# RoketAnaSistemSematik.net
KiCad netlist of a schematic drawn in Altium Designer
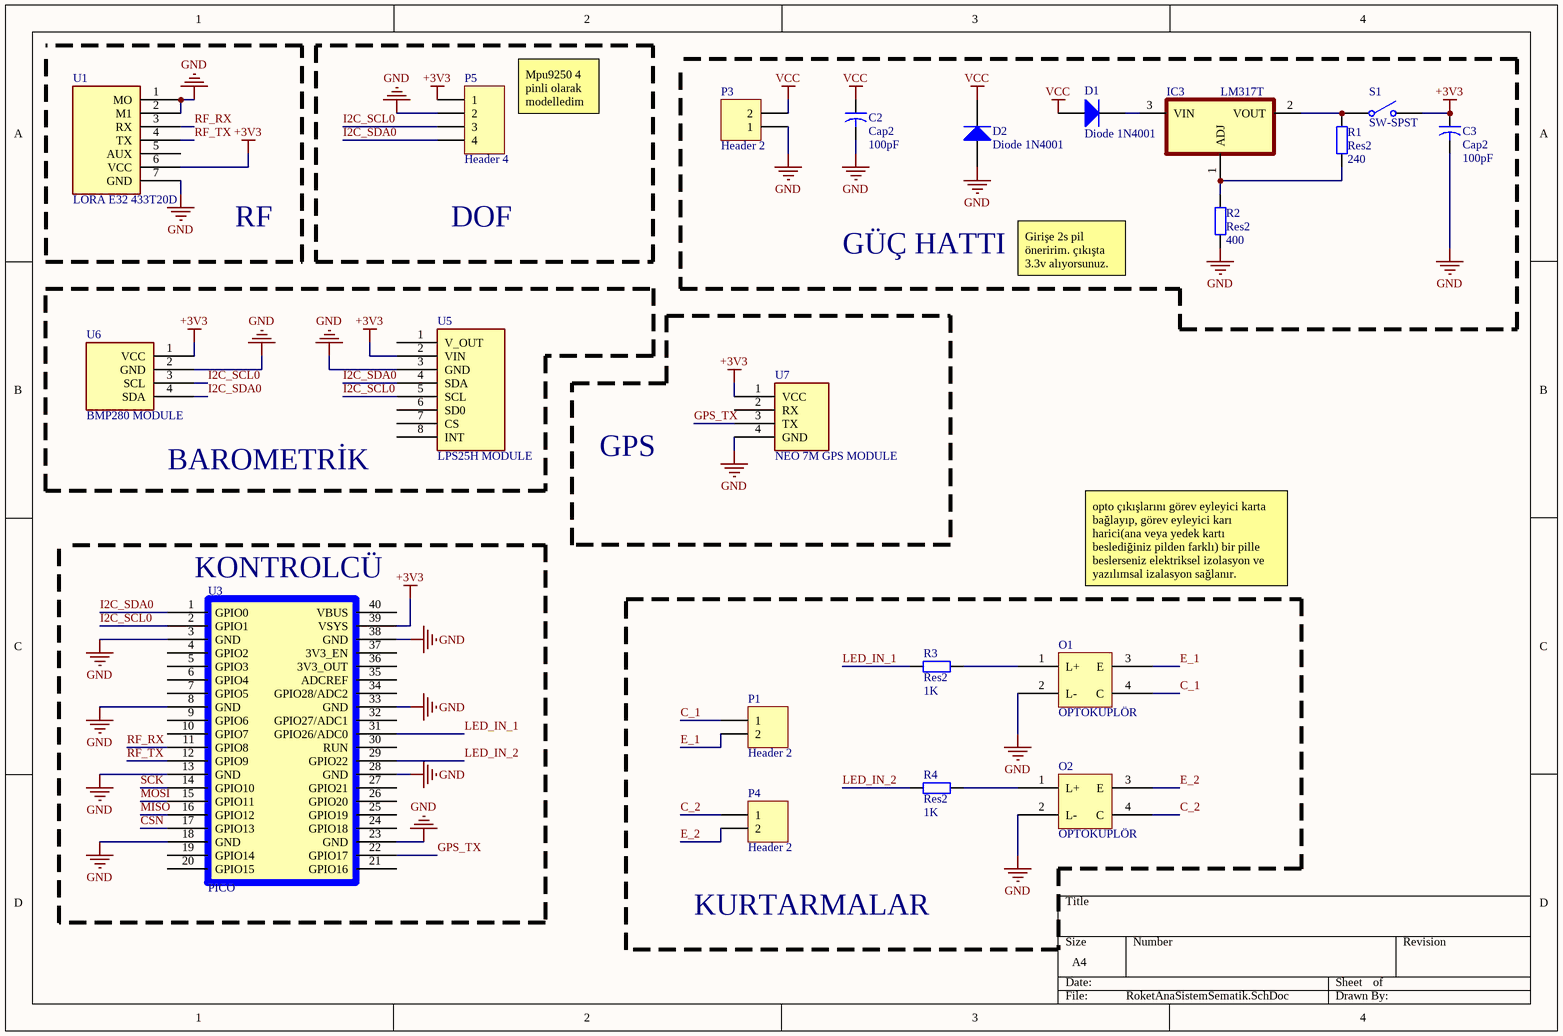
[diagram p0: RoketAnaSistemSematik.SchDoc]

(export (version "E")
  (design (tool "Eeschema 10.0.6"))
  (components
    (comp (ref "C2")
      (value "Cap2")
      (footprint "CAPR5-4X5")
      (description "Capacitor")
      (fields (field (name "ALTIUM_VALUE") "100pF") (field (name "PUBLISHER") "Altium Limited"))
      (libsource (lib "Miscellaneous Devices") (part "Cap2"))
    )
    (comp (ref "C3")
      (value "Cap2")
      (footprint "CAPR5-4X5")
      (description "Capacitor")
      (fields (field (name "ALTIUM_VALUE") "100pF") (field (name "PUBLISHER") "Altium Limited"))
      (libsource (lib "Miscellaneous Devices") (part "Cap2"))
    )
    (comp (ref "D1")
      (value "Diode 1N4001")
      (footprint "DO-41")
      (description "1 Amp General Purpose Rectifier")
      (fields (field (name "PUBLISHER") "Altium Limited"))
      (libsource (lib "Miscellaneous Devices") (part "Diode 1N4001"))
    )
    (comp (ref "D2")
      (value "Diode 1N4001")
      (footprint "DO-41")
      (description "1 Amp General Purpose Rectifier")
      (fields (field (name "PUBLISHER") "Altium Limited"))
      (libsource (lib "Miscellaneous Devices") (part "Diode 1N4001"))
    )
    (comp (ref "IC3")
      (value "LM317T")
      (footprint "LM317")
      (description "1.5-A, 40-V, adjustable linear voltage regulator 3-TO-220")
      (fields (field (name "MF") "Texas Instruments"))
      (libsource (lib "RoketAnaSistemSematikKütüphane") (part "LM317T"))
    )
    (comp (ref "O1")
      (value "OPTOKUPLÖR")
      (footprint "OPTOKUPLÖR")
      (libsource (lib "RoketAnaSistemSematikKütüphane") (part "OPTOKUPLÖR"))
    )
    (comp (ref "O2")
      (value "OPTOKUPLÖR")
      (footprint "OPTOKUPLÖR")
      (libsource (lib "RoketAnaSistemSematikKütüphane") (part "OPTOKUPLÖR"))
    )
    (comp (ref "P1")
      (value "Header 2")
      (footprint "HDR1X2")
      (description "Header, 2-Pin")
      (fields (field (name "PUBLISHER") "Altium Limited"))
      (libsource (lib "Miscellaneous Connectors") (part "Header 2"))
    )
    (comp (ref "P3")
      (value "Header 2")
      (footprint "HDR1X2")
      (description "Header, 2-Pin")
      (fields (field (name "PUBLISHER") "Altium Limited"))
      (libsource (lib "") (part "Header 2_1"))
    )
    (comp (ref "P4")
      (value "Header 2")
      (footprint "HDR1X2")
      (description "Header, 2-Pin")
      (fields (field (name "PUBLISHER") "Altium Limited"))
      (libsource (lib "Miscellaneous Connectors") (part "Header 2"))
    )
    (comp (ref "P5")
      (value "Header 4")
      (footprint "HDR1X4")
      (description "Header, 4-Pin")
      (fields (field (name "PUBLISHER") "Altium Limited"))
      (libsource (lib "Miscellaneous Connectors") (part "Header 4"))
    )
    (comp (ref "R1")
      (value "Res2")
      (footprint "AXIAL-0.4")
      (description "Resistor")
      (fields (field (name "ALTIUM_VALUE") "240") (field (name "PUBLISHER") "Altium Limited"))
      (libsource (lib "") (part "Res2_1"))
    )
    (comp (ref "R2")
      (value "Res2")
      (footprint "AXIAL-0.4")
      (description "Resistor")
      (fields (field (name "ALTIUM_VALUE") "400") (field (name "PUBLISHER") "Altium Limited"))
      (libsource (lib "") (part "Res2_2"))
    )
    (comp (ref "R3")
      (value "Res2")
      (footprint "AXIAL-0.4")
      (description "Resistor")
      (fields (field (name "ALTIUM_VALUE") "1K") (field (name "PUBLISHER") "Altium Limited"))
      (libsource (lib "Miscellaneous Devices") (part "Res2"))
    )
    (comp (ref "R4")
      (value "Res2")
      (footprint "AXIAL-0.4")
      (description "Resistor")
      (fields (field (name "ALTIUM_VALUE") "1K") (field (name "PUBLISHER") "Altium Limited"))
      (libsource (lib "Miscellaneous Devices") (part "Res2"))
    )
    (comp (ref "S1")
      (value "SW-SPST")
      (footprint "SPST-2")
      (description "Single-Pole, Single-Throw Switch")
      (fields (field (name "PUBLISHER") "Altium Limited"))
      (libsource (lib "Miscellaneous Devices") (part "SW-SPST"))
    )
    (comp (ref "U1")
      (value "LORA E32 433T20D")
      (footprint "LORA E32 433T20D")
      (description "LORA E32 433T20D RF MODULE")
      (libsource (lib "RoketAnaSistemSematikKütüphane") (part "LORA E32 433T20D"))
    )
    (comp (ref "U3")
      (value "PICO")
      (footprint "RASSBERY PI PICO")
      (description "133MHz MICROCONTROLLER")
      (libsource (lib "RoketAnaSistemSematikKütüphane") (part "Rasspberry Pi Pico"))
    )
    (comp (ref "U5")
      (value "LPS25H MODULE")
      (footprint "LPS25H SENSOR")
      (description "ALTITUDE, PRESSURE SENSOR MODULE")
      (libsource (lib "RoketAnaSistemSematikKütüphane") (part "LPS25H MODULE"))
    )
    (comp (ref "U6")
      (value "BMP280 MODULE")
      (footprint "BMP280 MODULE")
      (description "PRESSURE,ALTITUDE SENSOR MODULE")
      (libsource (lib "RoketAnaSistemSematikKütüphane") (part "BMP280 MODULE"))
    )
    (comp (ref "U7")
      (value "NEO 7M GPS MODULE")
      (footprint "NEO 7M GPS MODULE")
      (libsource (lib "RoketAnaSistemSematikKütüphane") (part "NEO 7M GPS MODULE"))
    )
  )
  (nets
    (net (code "1") (name "+3V3") (class "Default")
      (node (ref "C3") (pin "1") (pinfunction "1_1") (pintype "passive"))
      (node (ref "P5") (pin "1") (pinfunction "1_1") (pintype "passive"))
      (node (ref "S1") (pin "2") (pinfunction "NO_2") (pintype "passive"))
      (node (ref "U1") (pin "6") (pinfunction "VCC_6") (pintype "passive"))
      (node (ref "U3") (pin "39") (pinfunction "VSYS_39") (pintype "passive"))
      (node (ref "U5") (pin "2") (pinfunction "VIN_2") (pintype "passive"))
      (node (ref "U6") (pin "1") (pinfunction "VCC_1") (pintype "passive"))
      (node (ref "U7") (pin "1") (pinfunction "VCC_1") (pintype "passive"))
    )
    (net (code "2") (name "/CSN") (class "Default")
      (node (ref "U3") (pin "17") (pinfunction "GPIO13_17") (pintype "passive"))
    )
    (net (code "3") (name "/C_1") (class "Default")
      (node (ref "O1") (pin "4") (pinfunction "C_4") (pintype "passive"))
      (node (ref "P1") (pin "1") (pinfunction "1_1") (pintype "passive"))
    )
    (net (code "4") (name "/C_2") (class "Default")
      (node (ref "O2") (pin "4") (pinfunction "C_4") (pintype "passive"))
      (node (ref "P4") (pin "1") (pinfunction "1_1") (pintype "passive"))
    )
    (net (code "5") (name "/E_1") (class "Default")
      (node (ref "O1") (pin "3") (pinfunction "E_3") (pintype "passive"))
      (node (ref "P1") (pin "2") (pinfunction "2_2") (pintype "passive"))
    )
    (net (code "6") (name "/E_2") (class "Default")
      (node (ref "O2") (pin "3") (pinfunction "E_3") (pintype "passive"))
      (node (ref "P4") (pin "2") (pinfunction "2_2") (pintype "passive"))
    )
    (net (code "7") (name "/GPS_TX") (class "Default")
      (node (ref "U3") (pin "22") (pinfunction "GPIO17_22") (pintype "passive"))
      (node (ref "U7") (pin "3") (pinfunction "TX_3") (pintype "passive"))
    )
    (net (code "8") (name "/I2C_SCL0") (class "Default")
      (node (ref "P5") (pin "3") (pinfunction "3_3") (pintype "passive"))
      (node (ref "U3") (pin "2") (pinfunction "GPIO1_2") (pintype "passive"))
      (node (ref "U5") (pin "5") (pinfunction "SCL_5") (pintype "passive"))
      (node (ref "U6") (pin "3") (pinfunction "SCL_3") (pintype "passive"))
    )
    (net (code "9") (name "/I2C_SDA0") (class "Default")
      (node (ref "P5") (pin "4") (pinfunction "4_4") (pintype "passive"))
      (node (ref "U3") (pin "1") (pinfunction "GPIO0_1") (pintype "passive"))
      (node (ref "U5") (pin "4") (pinfunction "SDA_4") (pintype "passive"))
      (node (ref "U6") (pin "4") (pinfunction "SDA_4") (pintype "passive"))
    )
    (net (code "10") (name "/LED_IN_1") (class "Default")
      (node (ref "R3") (pin "2") (pinfunction "2_2") (pintype "passive"))
      (node (ref "U3") (pin "31") (pinfunction "GPIO26/ADC0_31") (pintype "passive"))
    )
    (net (code "11") (name "/LED_IN_2") (class "Default")
      (node (ref "R4") (pin "2") (pinfunction "2_2") (pintype "passive"))
      (node (ref "U3") (pin "29") (pinfunction "GPIO22_29") (pintype "passive"))
    )
    (net (code "12") (name "/MISO") (class "Default")
      (node (ref "U3") (pin "16") (pinfunction "GPIO12_16") (pintype "passive"))
    )
    (net (code "13") (name "/MOSI") (class "Default")
      (node (ref "U3") (pin "15") (pinfunction "GPIO11_15") (pintype "passive"))
    )
    (net (code "14") (name "/RF_RX") (class "Default")
      (node (ref "U1") (pin "3") (pinfunction "RX_3") (pintype "passive"))
      (node (ref "U3") (pin "11") (pinfunction "GPIO8_11") (pintype "passive"))
    )
    (net (code "15") (name "/RF_TX") (class "Default")
      (node (ref "U1") (pin "4") (pinfunction "TX_4") (pintype "passive"))
      (node (ref "U3") (pin "12") (pinfunction "GPIO9_12") (pintype "passive"))
    )
    (net (code "16") (name "/SCK") (class "Default")
      (node (ref "U3") (pin "14") (pinfunction "GPIO10_14") (pintype "passive"))
    )
    (net (code "17") (name "GND") (class "Default")
      (node (ref "C2") (pin "2") (pinfunction "2_2") (pintype "passive"))
      (node (ref "C3") (pin "2") (pinfunction "2_2") (pintype "passive"))
      (node (ref "D2") (pin "1") (pinfunction "A_1") (pintype "passive"))
      (node (ref "O1") (pin "2") (pinfunction "L-_2") (pintype "passive"))
      (node (ref "O2") (pin "2") (pinfunction "L-_2") (pintype "passive"))
      (node (ref "P3") (pin "1") (pinfunction "1_1") (pintype "passive"))
      (node (ref "P5") (pin "2") (pinfunction "2_2") (pintype "passive"))
      (node (ref "R2") (pin "2") (pinfunction "2_2") (pintype "passive"))
      (node (ref "U1") (pin "1") (pinfunction "MO_1") (pintype "passive"))
      (node (ref "U1") (pin "2") (pinfunction "M1_2") (pintype "passive"))
      (node (ref "U1") (pin "7") (pinfunction "GND_7") (pintype "passive"))
      (node (ref "U3") (pin "13") (pinfunction "GND_13") (pintype "passive"))
      (node (ref "U3") (pin "18") (pinfunction "GND_18") (pintype "passive"))
      (node (ref "U3") (pin "23") (pinfunction "GND_23") (pintype "passive"))
      (node (ref "U3") (pin "28") (pinfunction "GND_28") (pintype "passive"))
      (node (ref "U3") (pin "3") (pinfunction "GND_3") (pintype "passive"))
      (node (ref "U3") (pin "33") (pinfunction "GND_33") (pintype "passive"))
      (node (ref "U3") (pin "38") (pinfunction "GND_38") (pintype "passive"))
      (node (ref "U3") (pin "8") (pinfunction "GND_8") (pintype "passive"))
      (node (ref "U5") (pin "3") (pinfunction "GND_3") (pintype "passive"))
      (node (ref "U6") (pin "2") (pinfunction "GND_2") (pintype "passive"))
      (node (ref "U7") (pin "4") (pinfunction "GND_4") (pintype "passive"))
    )
    (net (code "18") (name "Net-(D1-K)") (class "Default")
      (node (ref "D1") (pin "2") (pinfunction "K_2") (pintype "passive"))
      (node (ref "IC3") (pin "3") (pinfunction "VIN_3") (pintype "passive"))
    )
    (net (code "19") (name "Net-(IC3-ADJ)") (class "Default")
      (node (ref "IC3") (pin "1") (pinfunction "ADJ_1") (pintype "passive"))
      (node (ref "R1") (pin "1") (pinfunction "1_1") (pintype "passive"))
      (node (ref "R2") (pin "1") (pinfunction "1_1") (pintype "passive"))
    )
    (net (code "20") (name "Net-(IC3-VOUT)") (class "Default")
      (node (ref "IC3") (pin "2") (pinfunction "VOUT_2") (pintype "passive"))
      (node (ref "R1") (pin "2") (pinfunction "2_2") (pintype "passive"))
      (node (ref "S1") (pin "1") (pinfunction "COMMON_1") (pintype "passive"))
    )
    (net (code "21") (name "Net-(O1-L+)") (class "Default")
      (node (ref "O1") (pin "1") (pinfunction "L+_1") (pintype "passive"))
      (node (ref "R3") (pin "1") (pinfunction "1_1") (pintype "passive"))
    )
    (net (code "22") (name "Net-(O2-L+)") (class "Default")
      (node (ref "O2") (pin "1") (pinfunction "L+_1") (pintype "passive"))
      (node (ref "R4") (pin "1") (pinfunction "1_1") (pintype "passive"))
    )
    (net (code "23") (name "VCC") (class "Default")
      (node (ref "C2") (pin "1") (pinfunction "1_1") (pintype "passive"))
      (node (ref "D1") (pin "1") (pinfunction "A_1") (pintype "passive"))
      (node (ref "D2") (pin "2") (pinfunction "K_2") (pintype "passive"))
      (node (ref "P3") (pin "2") (pinfunction "2_2") (pintype "passive"))
    )
    (net (code "24") (name "unconnected-(U1-AUX-Pad5)") (class "Default")
      (node (ref "U1") (pin "5") (pinfunction "AUX_5") (pintype "passive"))
    )
    (net (code "25") (name "unconnected-(U3-3V3_EN-Pad37)") (class "Default")
      (node (ref "U3") (pin "37") (pinfunction "3V3_EN_37") (pintype "passive"))
    )
    (net (code "26") (name "unconnected-(U3-3V3_OUT-Pad36)") (class "Default")
      (node (ref "U3") (pin "36") (pinfunction "3V3_OUT_36") (pintype "passive"))
    )
    (net (code "27") (name "unconnected-(U3-ADCREF-Pad35)") (class "Default")
      (node (ref "U3") (pin "35") (pinfunction "ADCREF_35") (pintype "passive"))
    )
    (net (code "28") (name "unconnected-(U3-GPIO2-Pad4)") (class "Default")
      (node (ref "U3") (pin "4") (pinfunction "GPIO2_4") (pintype "passive"))
    )
    (net (code "29") (name "unconnected-(U3-GPIO3-Pad5)") (class "Default")
      (node (ref "U3") (pin "5") (pinfunction "GPIO3_5") (pintype "passive"))
    )
    (net (code "30") (name "unconnected-(U3-GPIO4-Pad6)") (class "Default")
      (node (ref "U3") (pin "6") (pinfunction "GPIO4_6") (pintype "passive"))
    )
    (net (code "31") (name "unconnected-(U3-GPIO5-Pad7)") (class "Default")
      (node (ref "U3") (pin "7") (pinfunction "GPIO5_7") (pintype "passive"))
    )
    (net (code "32") (name "unconnected-(U3-GPIO6-Pad9)") (class "Default")
      (node (ref "U3") (pin "9") (pinfunction "GPIO6_9") (pintype "passive"))
    )
    (net (code "33") (name "unconnected-(U3-GPIO7-Pad10)") (class "Default")
      (node (ref "U3") (pin "10") (pinfunction "GPIO7_10") (pintype "passive"))
    )
    (net (code "34") (name "unconnected-(U3-GPIO14-Pad19)") (class "Default")
      (node (ref "U3") (pin "19") (pinfunction "GPIO14_19") (pintype "passive"))
    )
    (net (code "35") (name "unconnected-(U3-GPIO15-Pad20)") (class "Default")
      (node (ref "U3") (pin "20") (pinfunction "GPIO15_20") (pintype "passive"))
    )
    (net (code "36") (name "unconnected-(U3-GPIO16-Pad21)") (class "Default")
      (node (ref "U3") (pin "21") (pinfunction "GPIO16_21") (pintype "passive"))
    )
    (net (code "37") (name "unconnected-(U3-GPIO18-Pad24)") (class "Default")
      (node (ref "U3") (pin "24") (pinfunction "GPIO18_24") (pintype "passive"))
    )
    (net (code "38") (name "unconnected-(U3-GPIO19-Pad25)") (class "Default")
      (node (ref "U3") (pin "25") (pinfunction "GPIO19_25") (pintype "passive"))
    )
    (net (code "39") (name "unconnected-(U3-GPIO20-Pad26)") (class "Default")
      (node (ref "U3") (pin "26") (pinfunction "GPIO20_26") (pintype "passive"))
    )
    (net (code "40") (name "unconnected-(U3-GPIO21-Pad27)") (class "Default")
      (node (ref "U3") (pin "27") (pinfunction "GPIO21_27") (pintype "passive"))
    )
    (net (code "41") (name "unconnected-(U3-GPIO27{slash}ADC1-Pad32)") (class "Default")
      (node (ref "U3") (pin "32") (pinfunction "GPIO27/ADC1_32") (pintype "passive"))
    )
    (net (code "42") (name "unconnected-(U3-GPIO28{slash}ADC2-Pad34)") (class "Default")
      (node (ref "U3") (pin "34") (pinfunction "GPIO28/ADC2_34") (pintype "passive"))
    )
    (net (code "43") (name "unconnected-(U3-RUN-Pad30)") (class "Default")
      (node (ref "U3") (pin "30") (pinfunction "RUN_30") (pintype "passive"))
    )
    (net (code "44") (name "unconnected-(U3-VBUS-Pad40)") (class "Default")
      (node (ref "U3") (pin "40") (pinfunction "VBUS_40") (pintype "passive"))
    )
    (net (code "45") (name "unconnected-(U5-CS-Pad7)") (class "Default")
      (node (ref "U5") (pin "7") (pinfunction "CS_7") (pintype "passive"))
    )
    (net (code "46") (name "unconnected-(U5-INT-Pad8)") (class "Default")
      (node (ref "U5") (pin "8") (pinfunction "INT_8") (pintype "passive"))
    )
    (net (code "47") (name "unconnected-(U5-SD0-Pad6)") (class "Default")
      (node (ref "U5") (pin "6") (pinfunction "SD0_6") (pintype "passive"))
    )
    (net (code "48") (name "unconnected-(U5-V_OUT-Pad1)") (class "Default")
      (node (ref "U5") (pin "1") (pinfunction "V_OUT_1") (pintype "passive"))
    )
    (net (code "49") (name "unconnected-(U7-RX-Pad2)") (class "Default")
      (node (ref "U7") (pin "2") (pinfunction "RX_2") (pintype "passive"))
    )
  )
)
